# stepper_driver.net
KiCad netlist of a schematic drawn in Altium Designer
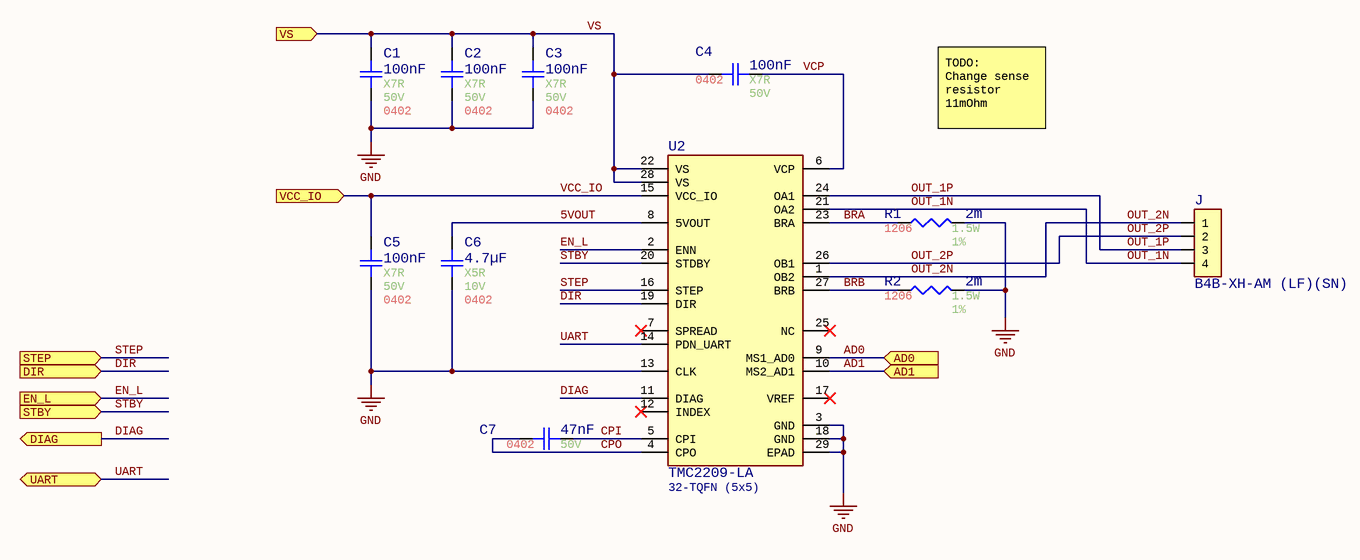
[diagram p0: stepper_driver.SchDoc]

(export (version "E")
  (design (tool "Eeschema 10.0.6"))
  (components
    (comp (ref "C1")
      (value "100nF")
      (footprint "Generic 0402 capacitor")
      (fields
        (field (name "TEMPERATURE COEFFICIENT") "X7R")
        (field (name "VOLTAGE RATING") "50V")
        (field (name "CASE/PACKAGE") "0402")
        (field (name "TOLERANCE") "10%")
        (field (name "Comment") "GRT155R71H104KE01D")
      )
      (libsource (lib "Raise Robotics") (part "Unpolarized Capacitor"))
    )
    (comp (ref "C2")
      (value "100nF")
      (footprint "Generic 0402 capacitor")
      (fields
        (field (name "TEMPERATURE COEFFICIENT") "X7R")
        (field (name "VOLTAGE RATING") "50V")
        (field (name "CASE/PACKAGE") "0402")
        (field (name "TOLERANCE") "10%")
        (field (name "Comment") "GRT155R71H104KE01D")
      )
      (libsource (lib "Raise Robotics") (part "Unpolarized Capacitor"))
    )
    (comp (ref "C3")
      (value "100nF")
      (footprint "Generic 0402 capacitor")
      (fields
        (field (name "TEMPERATURE COEFFICIENT") "X7R")
        (field (name "VOLTAGE RATING") "50V")
        (field (name "CASE/PACKAGE") "0402")
        (field (name "TOLERANCE") "10%")
        (field (name "Comment") "GRT155R71H104KE01D")
      )
      (libsource (lib "Raise Robotics") (part "Unpolarized Capacitor"))
    )
    (comp (ref "C4")
      (value "100nF")
      (footprint "Generic 0402 capacitor")
      (fields
        (field (name "TEMPERATURE COEFFICIENT") "X7R")
        (field (name "VOLTAGE RATING") "50V")
        (field (name "CASE/PACKAGE") "0402")
        (field (name "TOLERANCE") "10%")
        (field (name "Comment") "GRT155R71H104KE01D")
      )
      (libsource (lib "Raise Robotics") (part "Unpolarized Capacitor"))
    )
    (comp (ref "C5")
      (value "100nF")
      (footprint "Generic 0402 capacitor")
      (fields
        (field (name "TEMPERATURE COEFFICIENT") "X7R")
        (field (name "VOLTAGE RATING") "50V")
        (field (name "CASE/PACKAGE") "0402")
        (field (name "TOLERANCE") "10%")
        (field (name "Comment") "GRT155R71H104KE01D")
      )
      (libsource (lib "Raise Robotics") (part "Unpolarized Capacitor"))
    )
    (comp (ref "C6")
      (value "4.7µF")
      (footprint "Generic 0402 capacitor")
      (fields
        (field (name "TEMPERATURE COEFFICIENT") "X5R")
        (field (name "VOLTAGE RATING") "10V")
        (field (name "CASE/PACKAGE") "0402")
        (field (name "TOLERANCE") "0%")
        (field (name "Comment") "GRT155R61A475ME13D")
      )
      (libsource (lib "Raise Robotics") (part "Unpolarized Capacitor"))
    )
    (comp (ref "C7")
      (value "47nF")
      (footprint "Generic 0402 capacitor")
      (description "50V 47nF X7R ±10% 0402 Multilayer Ceramic Capacitors MLCC - SMD/SMT ROHS")
      (fields
        (field (name "VOLTAGE RATING") "50V")
        (field (name "CASE/PACKAGE") "0402")
        (field (name "TOLERANCE") "10%")
        (field (name "Comment") "GRM155R71H473KE14D")
      )
      (libsource (lib "Raise Robotics") (part "Unpolarized Capacitor"))
    )
    (comp (ref "J")
      (value "B4B-XH-AM (LF)(SN)")
      (footprint "FP-B4B-XH-AM_LF_SN-MFG")
      (description "Header, Xh, Top, 4Way, 2.5Mm, Boss;")
      (fields (field (name "MANUFACTURER") "JST"))
      (libsource (lib "Raise Robotics") (part "4 pin generic conn"))
    )
    (comp (ref "R1")
      (value "2m")
      (footprint "Generic 1206 resistor")
      (description "Res 0.002 Ohm 1% 1.5W 1206")
      (fields
        (field (name "POWER") "1.5W")
        (field (name "TOLERANCE") "1%")
        (field (name "CASE/PACKAGE") "1206")
        (field (name "MANUFACTURER PART NUMBER") "Blank")
        (field (name "Comment") "PA1206FRM670R002L")
      )
      (libsource (lib "Raise Robotics") (part "Resistor"))
    )
    (comp (ref "R2")
      (value "2m")
      (footprint "Generic 1206 resistor")
      (description "Res 0.002 Ohm 1% 1.5W 1206")
      (fields
        (field (name "POWER") "1.5W")
        (field (name "TOLERANCE") "1%")
        (field (name "CASE/PACKAGE") "1206")
        (field (name "MANUFACTURER PART NUMBER") "Blank")
        (field (name "Comment") "PA1206FRM670R002L")
      )
      (libsource (lib "Raise Robotics") (part "Resistor"))
    )
    (comp (ref "U2")
      (value "TMC2209-LA")
      (footprint "QFN-28_5x5x0.9mm_P0.5mm")
      (description "Step/Direction StealthChop Stepper Motor Driver Two-Phase 4.75V to 29V 28-Pin QFN Tray")
      (fields (field (name "MPN") "TMC5240ATJ+T") (field (name "CASE/PACKAGE") "32-TQFN (5x5)"))
      (libsource (lib "Raise Robotics") (part "TMC2209"))
    )
  )
  (nets
    (net (code "1") (name "/5VOUT") (class "Default")
      (node (ref "C6") (pin "2") (pinfunction "2_2") (pintype "passive"))
      (node (ref "U2") (pin "8") (pinfunction "5VOUT_8") (pintype "passive"))
    )
    (net (code "2") (name "/AD0") (class "Default")
      (node (ref "U2") (pin "9") (pinfunction "MS1_AD0_9") (pintype "passive"))
    )
    (net (code "3") (name "/AD1") (class "Default")
      (node (ref "U2") (pin "10") (pinfunction "MS2_AD1_10") (pintype "passive"))
    )
    (net (code "4") (name "/BRA") (class "Default")
      (node (ref "R1") (pin "1") (pinfunction "1_1") (pintype "passive"))
      (node (ref "U2") (pin "23") (pinfunction "BRA_23") (pintype "passive"))
    )
    (net (code "5") (name "/BRB") (class "Default")
      (node (ref "R2") (pin "1") (pinfunction "1_1") (pintype "passive"))
      (node (ref "U2") (pin "27") (pinfunction "BRB_27") (pintype "passive"))
    )
    (net (code "6") (name "/CPI") (class "Default")
      (node (ref "C7") (pin "1") (pinfunction "1_1") (pintype "passive"))
      (node (ref "U2") (pin "5") (pinfunction "CPI_5") (pintype "passive"))
    )
    (net (code "7") (name "/CPO") (class "Default")
      (node (ref "C7") (pin "2") (pinfunction "2_2") (pintype "passive"))
      (node (ref "U2") (pin "4") (pinfunction "CPO_4") (pintype "passive"))
    )
    (net (code "8") (name "/DIAG") (class "Default")
      (node (ref "U2") (pin "11") (pinfunction "DIAG_11") (pintype "passive"))
    )
    (net (code "9") (name "/DIR") (class "Default")
      (node (ref "U2") (pin "19") (pinfunction "DIR_19") (pintype "passive"))
    )
    (net (code "10") (name "/EN_L") (class "Default")
      (node (ref "U2") (pin "2") (pinfunction "ENN_2") (pintype "passive"))
    )
    (net (code "11") (name "/OUT_1N") (class "Default")
      (node (ref "J") (pin "4") (pinfunction "4_4") (pintype "passive"))
      (node (ref "U2") (pin "21") (pinfunction "OA2_21") (pintype "passive"))
    )
    (net (code "12") (name "/OUT_1P") (class "Default")
      (node (ref "J") (pin "3") (pinfunction "3_3") (pintype "passive"))
      (node (ref "U2") (pin "24") (pinfunction "OA1_24") (pintype "passive"))
    )
    (net (code "13") (name "/OUT_2N") (class "Default")
      (node (ref "J") (pin "1") (pinfunction "1_1") (pintype "passive"))
      (node (ref "U2") (pin "1") (pinfunction "OB2_1") (pintype "passive"))
    )
    (net (code "14") (name "/OUT_2P") (class "Default")
      (node (ref "J") (pin "2") (pinfunction "2_2") (pintype "passive"))
      (node (ref "U2") (pin "26") (pinfunction "OB1_26") (pintype "passive"))
    )
    (net (code "15") (name "/STBY") (class "Default")
      (node (ref "U2") (pin "20") (pinfunction "STDBY_20") (pintype "passive"))
    )
    (net (code "16") (name "/STEP") (class "Default")
      (node (ref "U2") (pin "16") (pinfunction "STEP_16") (pintype "passive"))
    )
    (net (code "17") (name "/UART") (class "Default")
      (node (ref "U2") (pin "14") (pinfunction "PDN_UART_14") (pintype "passive"))
    )
    (net (code "18") (name "/VCC_IO") (class "Default")
      (node (ref "C5") (pin "2") (pinfunction "2_2") (pintype "passive"))
      (node (ref "U2") (pin "15") (pinfunction "VCC_IO_15") (pintype "passive"))
    )
    (net (code "19") (name "/VCP") (class "Default")
      (node (ref "C4") (pin "1") (pinfunction "1_1") (pintype "passive"))
      (node (ref "U2") (pin "6") (pinfunction "VCP_6") (pintype "passive"))
    )
    (net (code "20") (name "/VS") (class "Default")
      (node (ref "C1") (pin "2") (pinfunction "2_2") (pintype "passive"))
      (node (ref "C2") (pin "2") (pinfunction "2_2") (pintype "passive"))
      (node (ref "C3") (pin "2") (pinfunction "2_2") (pintype "passive"))
      (node (ref "C4") (pin "2") (pinfunction "2_2") (pintype "passive"))
      (node (ref "U2") (pin "22") (pinfunction "VS_22") (pintype "passive"))
      (node (ref "U2") (pin "28") (pinfunction "VS_28") (pintype "passive"))
    )
    (net (code "21") (name "GND") (class "Default")
      (node (ref "C1") (pin "1") (pinfunction "1_1") (pintype "passive"))
      (node (ref "C2") (pin "1") (pinfunction "1_1") (pintype "passive"))
      (node (ref "C3") (pin "1") (pinfunction "1_1") (pintype "passive"))
      (node (ref "C5") (pin "1") (pinfunction "1_1") (pintype "passive"))
      (node (ref "C6") (pin "1") (pinfunction "1_1") (pintype "passive"))
      (node (ref "R1") (pin "2") (pinfunction "2_2") (pintype "passive"))
      (node (ref "R2") (pin "2") (pinfunction "2_2") (pintype "passive"))
      (node (ref "U2") (pin "13") (pinfunction "CLK_13") (pintype "passive"))
      (node (ref "U2") (pin "18") (pinfunction "GND_18") (pintype "passive"))
      (node (ref "U2") (pin "29") (pinfunction "EPAD_29") (pintype "passive"))
      (node (ref "U2") (pin "3") (pinfunction "GND_3") (pintype "passive"))
    )
    (net (code "22") (name "unconnected-(U2-INDEX-Pad12)") (class "Default")
      (node (ref "U2") (pin "12") (pinfunction "INDEX_12") (pintype "passive+no_connect"))
    )
    (net (code "23") (name "unconnected-(U2-NC-Pad25)") (class "Default")
      (node (ref "U2") (pin "25") (pinfunction "NC_25") (pintype "passive+no_connect"))
    )
    (net (code "24") (name "unconnected-(U2-SPREAD-Pad7)") (class "Default")
      (node (ref "U2") (pin "7") (pinfunction "SPREAD_7") (pintype "passive+no_connect"))
    )
    (net (code "25") (name "unconnected-(U2-VREF-Pad17)") (class "Default")
      (node (ref "U2") (pin "17") (pinfunction "VREF_17") (pintype "passive+no_connect"))
    )
  )
)
